# LCD_Controller_Baord.net
KiCad netlist of a schematic drawn in Altium Designer
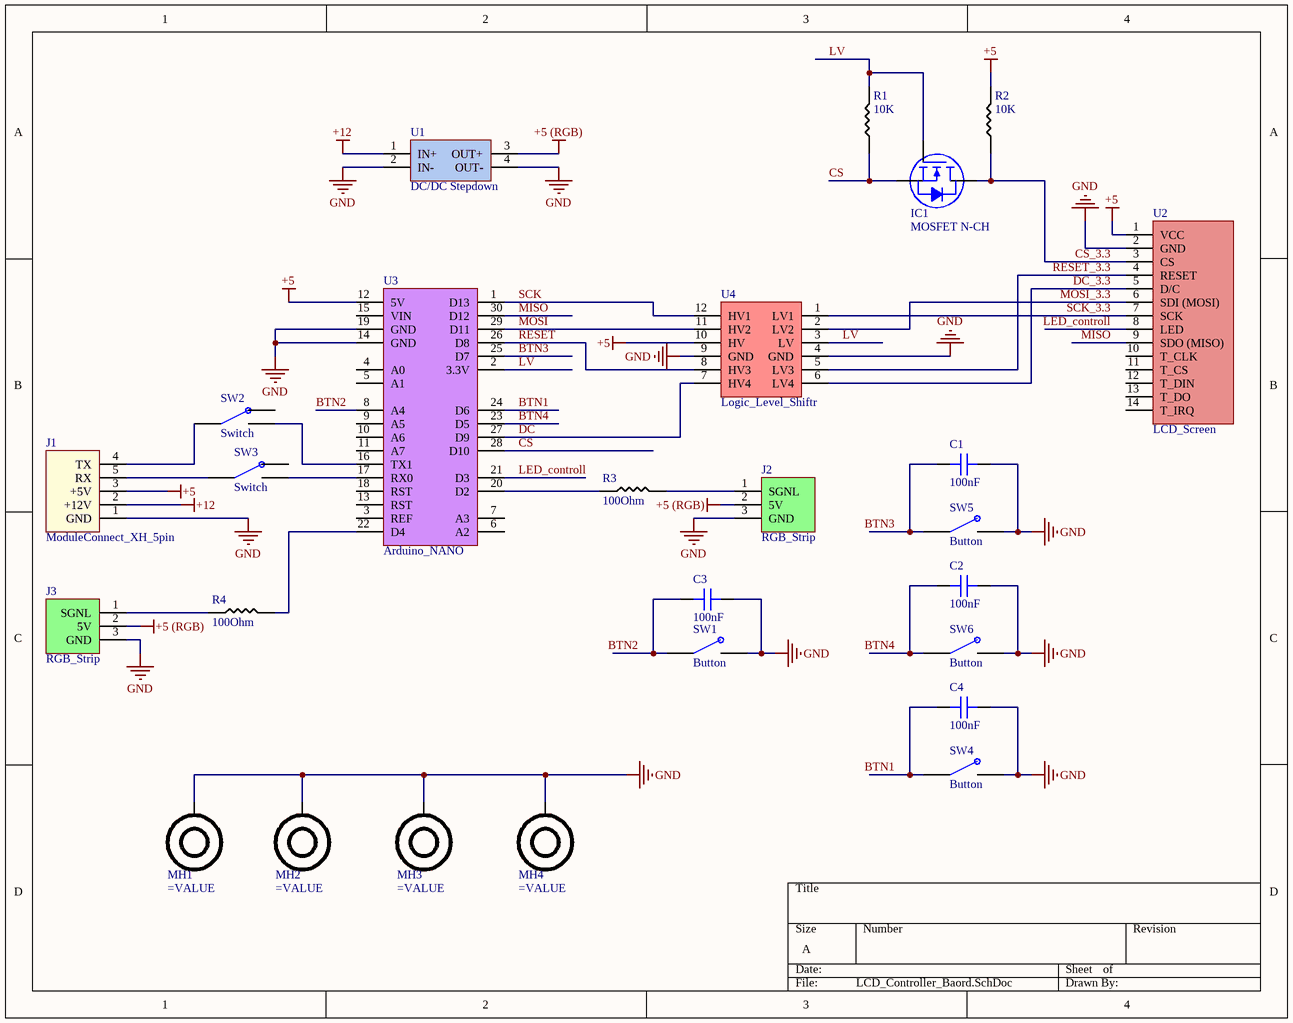
[diagram p0: LCD_Controller_Baord.SchDoc]

(export (version "E")
  (design (tool "Eeschema 10.0.6"))
  (components
    (comp (ref "C1")
      (value "100nF")
      (footprint "CAP 0603")
      (description "SMT Capacitor")
      (libsource (lib "LCD_Controller_Baord") (part "Capacitor"))
    )
    (comp (ref "C2")
      (value "100nF")
      (footprint "CAP 0603")
      (description "SMT Capacitor")
      (libsource (lib "LCD_Controller_Baord") (part "Capacitor"))
    )
    (comp (ref "C3")
      (value "100nF")
      (footprint "CAP 0603")
      (description "SMT Capacitor")
      (libsource (lib "LCD_Controller_Baord") (part "Capacitor"))
    )
    (comp (ref "C4")
      (value "100nF")
      (footprint "CAP 0603")
      (description "SMT Capacitor")
      (libsource (lib "LCD_Controller_Baord") (part "Capacitor"))
    )
    (comp (ref "IC1")
      (value "MOSFET N-CH")
      (footprint "SOT-23")
      (libsource (lib "LCD_Controller_Baord") (part "MOSFET N-CH"))
    )
    (comp (ref "J1")
      (value "ModuleConnect_XH_5pin")
      (footprint "JST S5B-XH-A")
      (libsource (lib "LCD_Controller_Baord") (part "ModuleConnect_XH_5pin"))
    )
    (comp (ref "J2")
      (value "RGB_Strip")
      (footprint "JST_S3B-XH-A(LF)(SN)")
      (libsource (lib "LCD_Controller_Baord") (part "RGB_Strip"))
    )
    (comp (ref "J3")
      (value "RGB_Strip")
      (footprint "JST_S3B-XH-A(LF)(SN)")
      (libsource (lib "") (part "RGB_Strip_1"))
    )
    (comp (ref "MH1")
      (value "~")
      (footprint "SCREW_M3.0")
      (libsource (lib "LCD_Controller_Baord") (part "SCREW"))
    )
    (comp (ref "MH2")
      (value "~")
      (footprint "SCREW_M3.0")
      (libsource (lib "LCD_Controller_Baord") (part "SCREW"))
    )
    (comp (ref "MH3")
      (value "~")
      (footprint "SCREW_M3.0")
      (libsource (lib "LCD_Controller_Baord") (part "SCREW"))
    )
    (comp (ref "MH4")
      (value "~")
      (footprint "SCREW_M3.0")
      (libsource (lib "LCD_Controller_Baord") (part "SCREW"))
    )
    (comp (ref "R1")
      (value "10K")
      (footprint "RES 0603")
      (description "100Ω ±1% 0.25W ±100ppm/℃ 1206 Chip Resistor - Surface Mount RoHS")
      (fields (field (name "LCSC PART#") "C17901") (field (name "MFR PART #") "1206W4F1000T5E"))
      (libsource (lib "LCD_Controller_Baord") (part "R_100Ohm_1206"))
    )
    (comp (ref "R2")
      (value "10K")
      (footprint "RES 0603")
      (description "100Ω ±1% 0.25W ±100ppm/℃ 1206 Chip Resistor - Surface Mount RoHS")
      (fields (field (name "LCSC PART#") "C17901") (field (name "MFR PART #") "1206W4F1000T5E"))
      (libsource (lib "LCD_Controller_Baord") (part "R_100Ohm_1206"))
    )
    (comp (ref "R3")
      (value "100Ohm")
      (footprint "RES 0603")
      (description "100Ω ±1% 0.25W ±100ppm/℃ 1206 Chip Resistor - Surface Mount RoHS")
      (fields (field (name "LCSC PART#") "C17901") (field (name "MFR PART #") "1206W4F1000T5E"))
      (libsource (lib "LCD_Controller_Baord") (part "R_100Ohm_1206"))
    )
    (comp (ref "R4")
      (value "100Ohm")
      (footprint "RES 0603")
      (description "100Ω ±1% 0.25W ±100ppm/℃ 1206 Chip Resistor - Surface Mount RoHS")
      (fields (field (name "LCSC PART#") "C17901") (field (name "MFR PART #") "1206W4F1000T5E"))
      (libsource (lib "LCD_Controller_Baord") (part "R_100Ohm_1206"))
    )
    (comp (ref "SW1")
      (value "Button")
      (footprint "SW_FSM8JH")
      (libsource (lib "LCD_Controller_Baord") (part "Button"))
    )
    (comp (ref "SW2")
      (value "Switch")
      (footprint "EG1218")
      (libsource (lib "LCD_Controller_Baord") (part "Switch"))
    )
    (comp (ref "SW3")
      (value "Switch")
      (footprint "EG1218")
      (libsource (lib "LCD_Controller_Baord") (part "Switch"))
    )
    (comp (ref "SW4")
      (value "Button")
      (footprint "SW_FSM8JH")
      (libsource (lib "LCD_Controller_Baord") (part "Button"))
    )
    (comp (ref "SW5")
      (value "Button")
      (footprint "SW_FSM8JH")
      (libsource (lib "LCD_Controller_Baord") (part "Button"))
    )
    (comp (ref "SW6")
      (value "Button")
      (footprint "SW_FSM8JH")
      (libsource (lib "LCD_Controller_Baord") (part "Button"))
    )
    (comp (ref "U1")
      (value "DC/DC Stepdown")
      (footprint "DC/DC Stepdown")
      (libsource (lib "LCD_Controller_Baord") (part "DC/DC Stepdown"))
    )
    (comp (ref "U2")
      (value "LCD_Screen")
      (footprint "14_PIN_LCD")
      (libsource (lib "LCD_Controller_Baord") (part "LCD_Screen"))
    )
    (comp (ref "U3")
      (value "Arduino_NANO")
      (footprint "MODULE_ABX00028")
      (libsource (lib "LCD_Controller_Baord") (part "Arduino_NANO"))
    )
    (comp (ref "U4")
      (value "Logic_Level_Shiftr")
      (footprint "Logic_Shifter")
      (libsource (lib "LCD_Controller_Baord") (part "Logic_Level_Shiftr"))
    )
  )
  (nets
    (net (code "1") (name "+5") (class "Default")
      (node (ref "J1") (pin "3") (pinfunction "+5V_3") (pintype "passive"))
      (node (ref "R2") (pin "2") (pinfunction "2_2") (pintype "passive"))
      (node (ref "U2") (pin "1") (pinfunction "VCC_1") (pintype "passive"))
      (node (ref "U3") (pin "12") (pinfunction "5V_12") (pintype "passive"))
      (node (ref "U4") (pin "10") (pinfunction "HV_10") (pintype "passive"))
    )
    (net (code "2") (name "+5 (RGB)") (class "Default")
      (node (ref "J2") (pin "2") (pinfunction "5V_2") (pintype "passive"))
      (node (ref "J3") (pin "2") (pinfunction "5V_2") (pintype "passive"))
      (node (ref "U1") (pin "3") (pinfunction "OUT+_3") (pintype "passive"))
    )
    (net (code "3") (name "+12") (class "Default")
      (node (ref "J1") (pin "2") (pinfunction "+12V_2") (pintype "passive"))
      (node (ref "U1") (pin "1") (pinfunction "IN+_1") (pintype "passive"))
    )
    (net (code "4") (name "/BTN1") (class "Default")
      (node (ref "C4") (pin "1") (pinfunction "1_1") (pintype "passive"))
      (node (ref "SW4") (pin "1") (pinfunction "1_1") (pintype "passive"))
      (node (ref "U3") (pin "24") (pinfunction "D6_24") (pintype "passive"))
    )
    (net (code "5") (name "/BTN2") (class "Default")
      (node (ref "C3") (pin "1") (pinfunction "1_1") (pintype "passive"))
      (node (ref "SW1") (pin "1") (pinfunction "1_1") (pintype "passive"))
      (node (ref "U3") (pin "8") (pinfunction "A4_8") (pintype "passive"))
    )
    (net (code "6") (name "/BTN3") (class "Default")
      (node (ref "C1") (pin "1") (pinfunction "1_1") (pintype "passive"))
      (node (ref "SW5") (pin "1") (pinfunction "1_1") (pintype "passive"))
      (node (ref "U3") (pin "25") (pinfunction "D7_25") (pintype "passive"))
    )
    (net (code "7") (name "/BTN4") (class "Default")
      (node (ref "C2") (pin "1") (pinfunction "1_1") (pintype "passive"))
      (node (ref "SW6") (pin "1") (pinfunction "1_1") (pintype "passive"))
      (node (ref "U3") (pin "23") (pinfunction "D5_23") (pintype "passive"))
    )
    (net (code "8") (name "/CS") (class "Default")
      (node (ref "IC1") (pin "2") (pinfunction "S_2") (pintype "passive"))
      (node (ref "R1") (pin "1") (pinfunction "1_1") (pintype "passive"))
      (node (ref "U3") (pin "28") (pinfunction "D10_28") (pintype "passive"))
    )
    (net (code "9") (name "/CS_3.3") (class "Default")
      (node (ref "IC1") (pin "3") (pinfunction "D_3") (pintype "passive"))
      (node (ref "R2") (pin "1") (pinfunction "1_1") (pintype "passive"))
      (node (ref "U2") (pin "3") (pinfunction "CS_3") (pintype "passive"))
    )
    (net (code "10") (name "/DC") (class "Default")
      (node (ref "U3") (pin "27") (pinfunction "D9_27") (pintype "passive"))
      (node (ref "U4") (pin "7") (pinfunction "HV4_7") (pintype "passive"))
    )
    (net (code "11") (name "/DC_3.3") (class "Default")
      (node (ref "U2") (pin "5") (pinfunction "D/C_5") (pintype "passive"))
      (node (ref "U4") (pin "6") (pinfunction "LV4_6") (pintype "passive"))
    )
    (net (code "12") (name "/LED_controll") (class "Default")
      (node (ref "U2") (pin "8") (pinfunction "LED_8") (pintype "passive"))
      (node (ref "U3") (pin "21") (pinfunction "D3_21") (pintype "passive"))
    )
    (net (code "13") (name "/LV") (class "Default")
      (node (ref "IC1") (pin "1") (pinfunction "G_1") (pintype "passive"))
      (node (ref "R1") (pin "2") (pinfunction "2_2") (pintype "passive"))
      (node (ref "U3") (pin "2") (pinfunction "3.3V_2") (pintype "passive"))
      (node (ref "U4") (pin "3") (pinfunction "LV_3") (pintype "passive"))
    )
    (net (code "14") (name "/MISO") (class "Default")
      (node (ref "U2") (pin "9") (pinfunction "SDO_(MISO)_9") (pintype "passive"))
      (node (ref "U3") (pin "30") (pinfunction "D12_30") (pintype "passive"))
    )
    (net (code "15") (name "/MOSI") (class "Default")
      (node (ref "U3") (pin "29") (pinfunction "D11_29") (pintype "passive"))
      (node (ref "U4") (pin "11") (pinfunction "HV2_11") (pintype "passive"))
    )
    (net (code "16") (name "/MOSI_3.3") (class "Default")
      (node (ref "U2") (pin "6") (pinfunction "SDI_(MOSI)_6") (pintype "passive"))
      (node (ref "U4") (pin "2") (pinfunction "LV2_2") (pintype "passive"))
    )
    (net (code "17") (name "/RESET") (class "Default")
      (node (ref "U3") (pin "26") (pinfunction "D8_26") (pintype "passive"))
      (node (ref "U4") (pin "8") (pinfunction "HV3_8") (pintype "passive"))
    )
    (net (code "18") (name "/RESET_3.3") (class "Default")
      (node (ref "U2") (pin "4") (pinfunction "RESET_4") (pintype "passive"))
      (node (ref "U4") (pin "5") (pinfunction "LV3_5") (pintype "passive"))
    )
    (net (code "19") (name "/SCK") (class "Default")
      (node (ref "U3") (pin "1") (pinfunction "D13_1") (pintype "passive"))
      (node (ref "U4") (pin "12") (pinfunction "HV1_12") (pintype "passive"))
    )
    (net (code "20") (name "/SCK_3.3") (class "Default")
      (node (ref "U2") (pin "7") (pinfunction "SCK_7") (pintype "passive"))
      (node (ref "U4") (pin "1") (pinfunction "LV1_1") (pintype "passive"))
    )
    (net (code "21") (name "GND") (class "Default")
      (node (ref "C1") (pin "2") (pinfunction "2_2") (pintype "passive"))
      (node (ref "C2") (pin "2") (pinfunction "2_2") (pintype "passive"))
      (node (ref "C3") (pin "2") (pinfunction "2_2") (pintype "passive"))
      (node (ref "C4") (pin "2") (pinfunction "2_2") (pintype "passive"))
      (node (ref "J1") (pin "1") (pinfunction "GND_1") (pintype "passive"))
      (node (ref "J2") (pin "3") (pinfunction "GND_3") (pintype "passive"))
      (node (ref "J3") (pin "3") (pinfunction "GND_3") (pintype "passive"))
      (node (ref "MH1") (pin "1") (pinfunction "1_1") (pintype "passive"))
      (node (ref "MH2") (pin "1") (pinfunction "1_1") (pintype "passive"))
      (node (ref "MH3") (pin "1") (pinfunction "1_1") (pintype "passive"))
      (node (ref "MH4") (pin "1") (pinfunction "1_1") (pintype "passive"))
      (node (ref "SW1") (pin "2") (pinfunction "2_2") (pintype "passive"))
      (node (ref "SW4") (pin "2") (pinfunction "2_2") (pintype "passive"))
      (node (ref "SW5") (pin "2") (pinfunction "2_2") (pintype "passive"))
      (node (ref "SW6") (pin "2") (pinfunction "2_2") (pintype "passive"))
      (node (ref "U1") (pin "2") (pinfunction "IN-_2") (pintype "passive"))
      (node (ref "U1") (pin "4") (pinfunction "OUT-_4") (pintype "passive"))
      (node (ref "U2") (pin "2") (pinfunction "GND_2") (pintype "passive"))
      (node (ref "U3") (pin "14") (pinfunction "GND_14") (pintype "passive"))
      (node (ref "U3") (pin "19") (pinfunction "GND_19") (pintype "passive"))
      (node (ref "U4") (pin "4") (pinfunction "GND_4") (pintype "passive"))
      (node (ref "U4") (pin "9") (pinfunction "GND_9") (pintype "passive"))
    )
    (net (code "22") (name "Net-(J1-RX)") (class "Default")
      (node (ref "J1") (pin "5") (pinfunction "RX_5") (pintype "passive"))
      (node (ref "SW3") (pin "2") (pinfunction "2_2") (pintype "passive"))
    )
    (net (code "23") (name "Net-(J1-TX)") (class "Default")
      (node (ref "J1") (pin "4") (pinfunction "TX_4") (pintype "passive"))
      (node (ref "SW2") (pin "2") (pinfunction "2_2") (pintype "passive"))
    )
    (net (code "24") (name "Net-(J2-SGNL)") (class "Default")
      (node (ref "J2") (pin "1") (pinfunction "SGNL_1") (pintype "passive"))
      (node (ref "R3") (pin "2") (pinfunction "2_2") (pintype "passive"))
    )
    (net (code "25") (name "Net-(J3-SGNL)") (class "Default")
      (node (ref "J3") (pin "1") (pinfunction "SGNL_1") (pintype "passive"))
      (node (ref "R4") (pin "2") (pinfunction "2_2") (pintype "passive"))
    )
    (net (code "26") (name "Net-(U3-D2)") (class "Default")
      (node (ref "R3") (pin "1") (pinfunction "1_1") (pintype "passive"))
      (node (ref "U3") (pin "20") (pinfunction "D2_20") (pintype "passive"))
    )
    (net (code "27") (name "Net-(U3-D4)") (class "Default")
      (node (ref "R4") (pin "1") (pinfunction "1_1") (pintype "passive"))
      (node (ref "U3") (pin "22") (pinfunction "D4_22") (pintype "passive"))
    )
    (net (code "28") (name "Net-(U3-RX0)") (class "Default")
      (node (ref "SW3") (pin "3") (pinfunction "3_3") (pintype "passive"))
      (node (ref "U3") (pin "17") (pinfunction "RX0_17") (pintype "passive"))
    )
    (net (code "29") (name "Net-(U3-TX1)") (class "Default")
      (node (ref "SW2") (pin "3") (pinfunction "3_3") (pintype "passive"))
      (node (ref "U3") (pin "16") (pinfunction "TX1_16") (pintype "passive"))
    )
    (net (code "30") (name "unconnected-(SW2-Pad1)") (class "Default")
      (node (ref "SW2") (pin "1") (pinfunction "1_1") (pintype "passive"))
    )
    (net (code "31") (name "unconnected-(SW3-Pad1)") (class "Default")
      (node (ref "SW3") (pin "1") (pinfunction "1_1") (pintype "passive"))
    )
    (net (code "32") (name "unconnected-(U2-T_CLK-Pad10)") (class "Default")
      (node (ref "U2") (pin "10") (pinfunction "T_CLK_10") (pintype "passive"))
    )
    (net (code "33") (name "unconnected-(U2-T_CS-Pad11)") (class "Default")
      (node (ref "U2") (pin "11") (pinfunction "T_CS_11") (pintype "passive"))
    )
    (net (code "34") (name "unconnected-(U2-T_DIN-Pad12)") (class "Default")
      (node (ref "U2") (pin "12") (pinfunction "T_DIN_12") (pintype "passive"))
    )
    (net (code "35") (name "unconnected-(U2-T_DO-Pad13)") (class "Default")
      (node (ref "U2") (pin "13") (pinfunction "T_DO_13") (pintype "passive"))
    )
    (net (code "36") (name "unconnected-(U2-T_IRQ-Pad14)") (class "Default")
      (node (ref "U2") (pin "14") (pinfunction "T_IRQ_14") (pintype "passive"))
    )
    (net (code "37") (name "unconnected-(U3-A0-Pad4)") (class "Default")
      (node (ref "U3") (pin "4") (pinfunction "A0_4") (pintype "passive"))
    )
    (net (code "38") (name "unconnected-(U3-A1-Pad5)") (class "Default")
      (node (ref "U3") (pin "5") (pinfunction "A1_5") (pintype "passive"))
    )
    (net (code "39") (name "unconnected-(U3-A2-Pad6)") (class "Default")
      (node (ref "U3") (pin "6") (pinfunction "A2_6") (pintype "passive"))
    )
    (net (code "40") (name "unconnected-(U3-A3-Pad7)") (class "Default")
      (node (ref "U3") (pin "7") (pinfunction "A3_7") (pintype "passive"))
    )
    (net (code "41") (name "unconnected-(U3-A5-Pad9)") (class "Default")
      (node (ref "U3") (pin "9") (pinfunction "A5_9") (pintype "passive"))
    )
    (net (code "42") (name "unconnected-(U3-A6-Pad10)") (class "Default")
      (node (ref "U3") (pin "10") (pinfunction "A6_10") (pintype "passive"))
    )
    (net (code "43") (name "unconnected-(U3-A7-Pad11)") (class "Default")
      (node (ref "U3") (pin "11") (pinfunction "A7_11") (pintype "passive"))
    )
    (net (code "44") (name "unconnected-(U3-REF-Pad3)") (class "Default")
      (node (ref "U3") (pin "3") (pinfunction "REF_3") (pintype "passive"))
    )
    (net (code "45") (name "unconnected-(U3-RST-Pad13)") (class "Default")
      (node (ref "U3") (pin "13") (pinfunction "RST_13") (pintype "passive"))
    )
    (net (code "46") (name "unconnected-(U3-RST-Pad18)") (class "Default")
      (node (ref "U3") (pin "18") (pinfunction "RST_18") (pintype "passive"))
    )
    (net (code "47") (name "unconnected-(U3-VIN-Pad15)") (class "Default")
      (node (ref "U3") (pin "15") (pinfunction "VIN_15") (pintype "passive"))
    )
  )
)
